# NSE2022_BATTERY_ver0.net
KiCad netlist of a schematic drawn in EAGLE
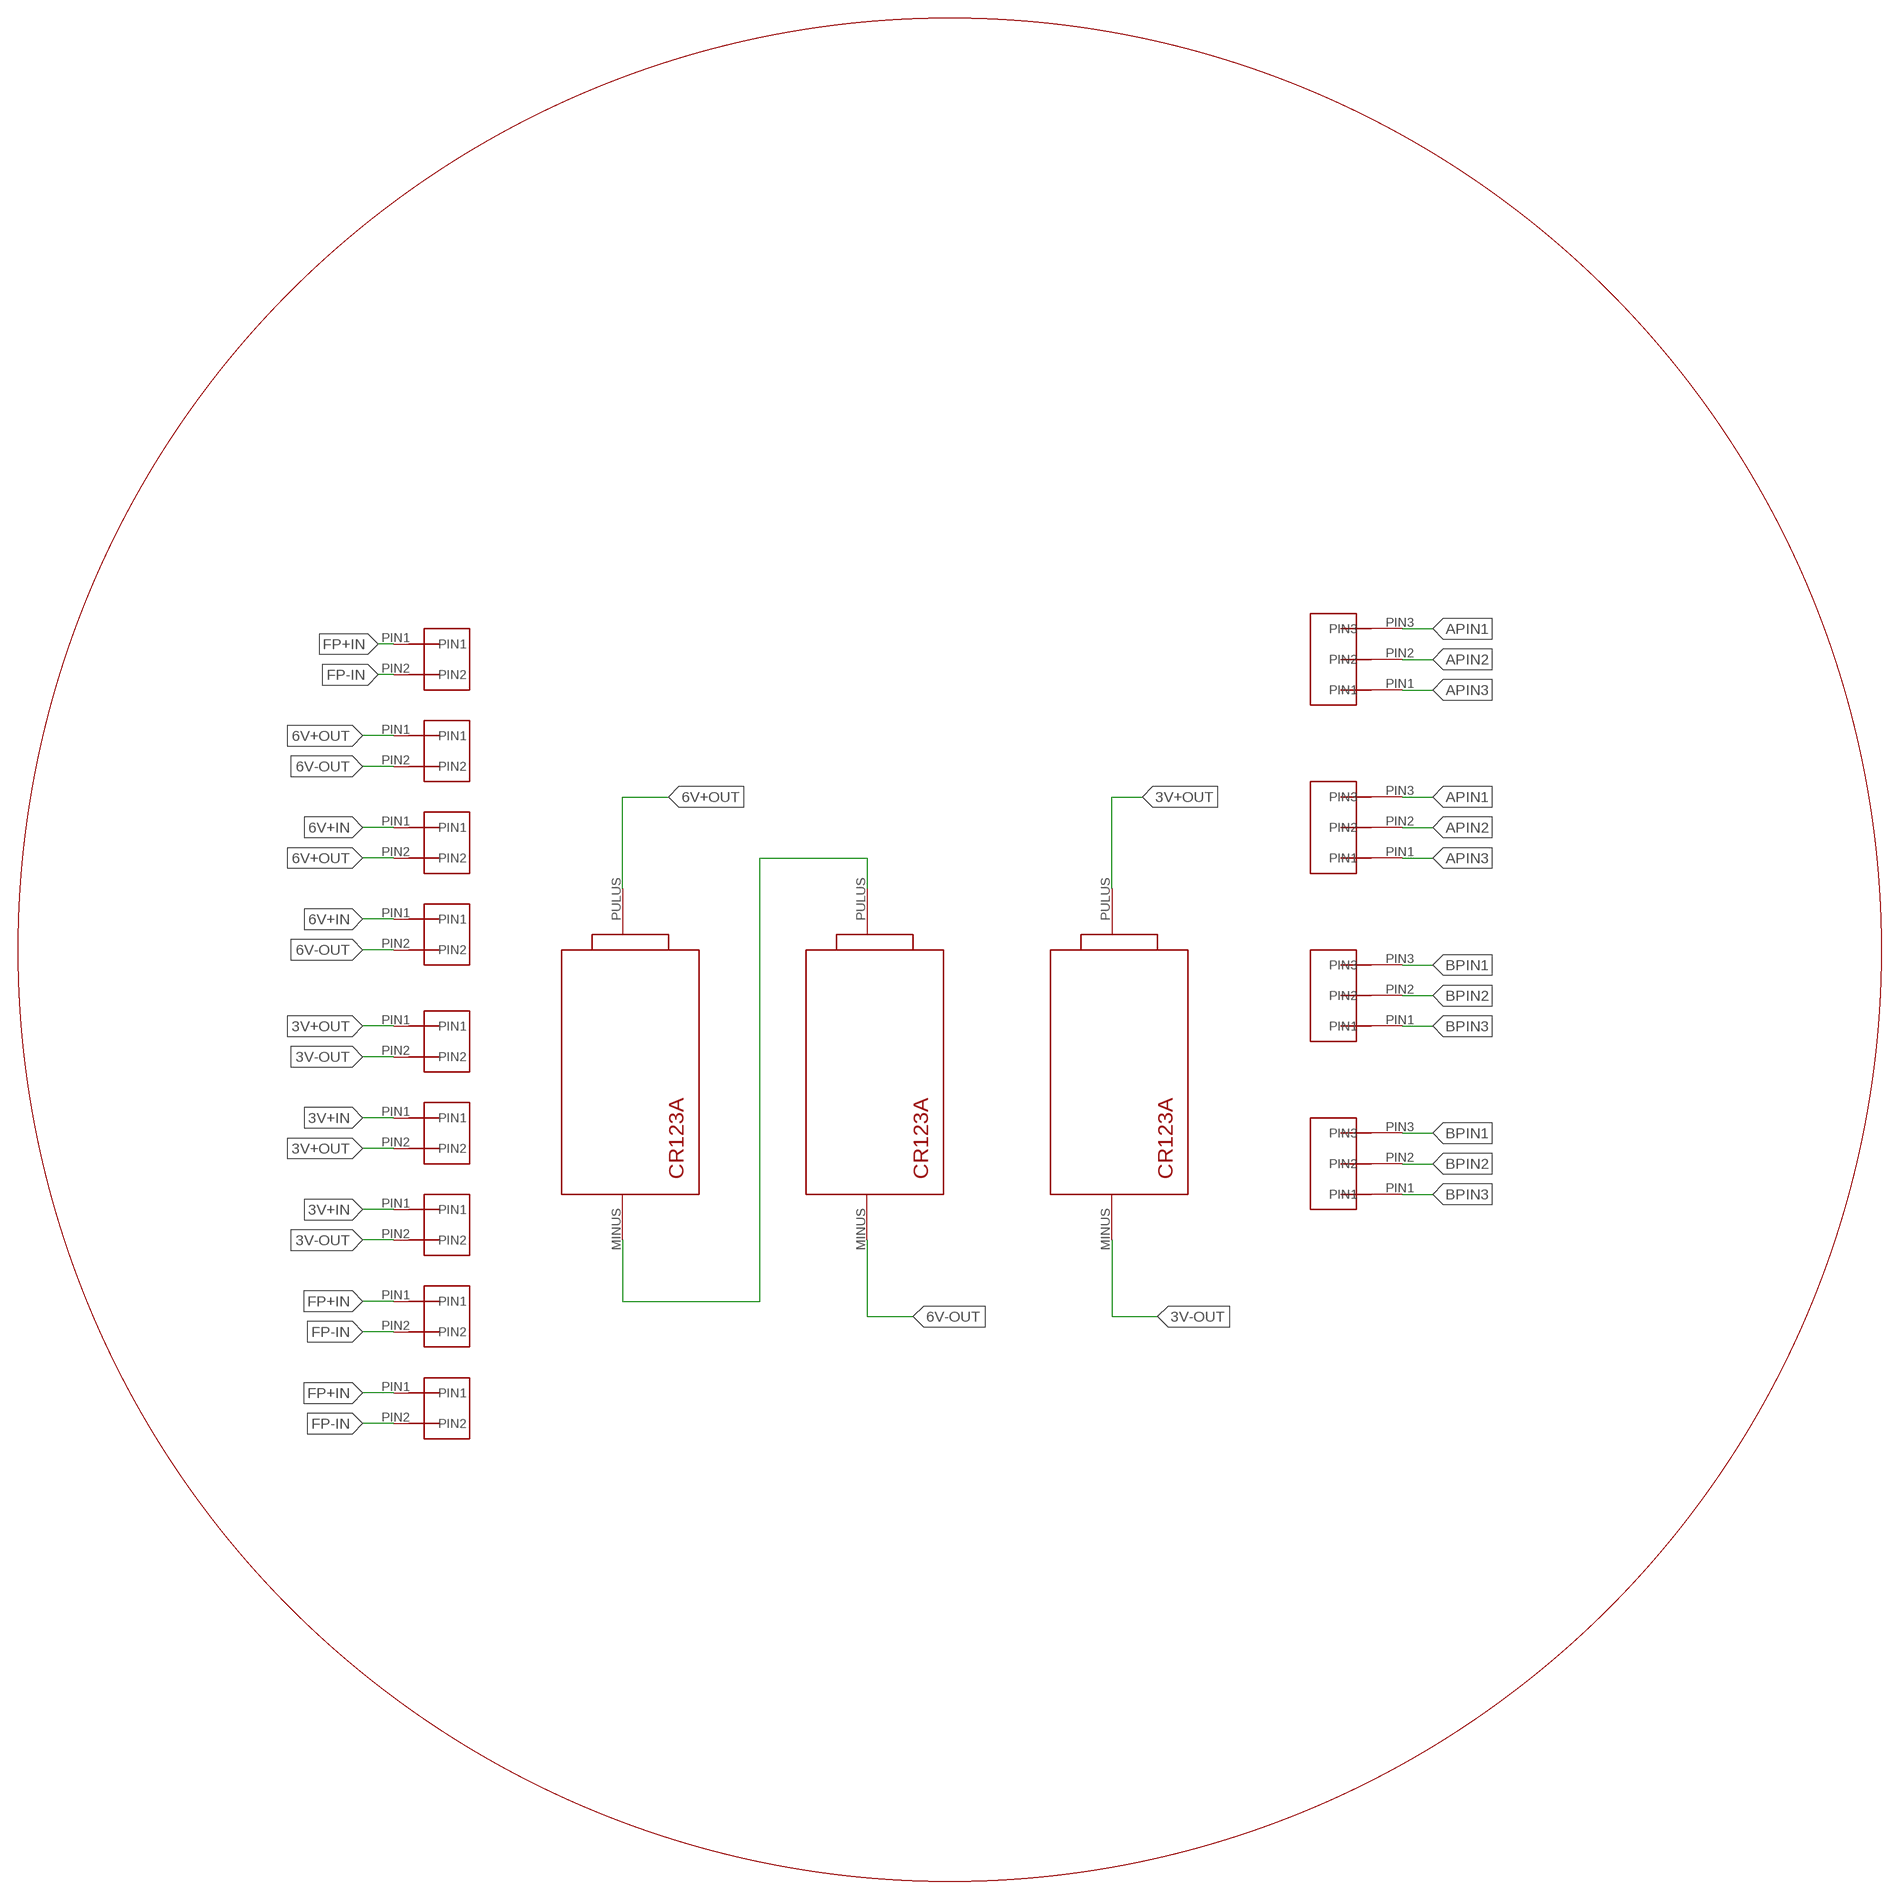
[diagram p0: schematic, sheet 1]

(export (version "E")
  (design (tool "Eeschema 10.0.6"))
  (components
    (comp (ref "U$25")
      (value "CR123A")
      (footprint "eagle-import:CR123A")
      (libsource (lib "eagle-import") (part "CR123A"))
    )
    (comp (ref "U$34")
      (value "CR123A")
      (footprint "eagle-import:CR123A")
      (libsource (lib "eagle-import") (part "CR123A"))
    )
    (comp (ref "U$38")
      (value "CR123A")
      (footprint "eagle-import:CR123A")
      (libsource (lib "eagle-import") (part "CR123A"))
    )
    (comp (ref "U$41")
      (value "2PIN")
      (footprint "eagle-import:2PIN")
      (libsource (lib "eagle-import") (part "2PIN"))
    )
    (comp (ref "U$45")
      (value "2PIN")
      (footprint "eagle-import:2PIN")
      (libsource (lib "eagle-import") (part "2PIN"))
    )
    (comp (ref "U$56")
      (value "2PIN")
      (footprint "eagle-import:2PIN")
      (libsource (lib "eagle-import") (part "2PIN"))
    )
    (comp (ref "U$57")
      (value "2PIN")
      (footprint "eagle-import:2PIN")
      (libsource (lib "eagle-import") (part "2PIN"))
    )
    (comp (ref "U$58")
      (value "2PIN")
      (footprint "eagle-import:2PIN")
      (libsource (lib "eagle-import") (part "2PIN"))
    )
    (comp (ref "U$59")
      (value "3PIN")
      (footprint "eagle-import:3PIN")
      (libsource (lib "eagle-import") (part "3PIN"))
    )
    (comp (ref "U$60")
      (value "3PIN")
      (footprint "eagle-import:3PIN")
      (libsource (lib "eagle-import") (part "3PIN"))
    )
    (comp (ref "U$61")
      (value "3PIN")
      (footprint "eagle-import:3PIN")
      (libsource (lib "eagle-import") (part "3PIN"))
    )
    (comp (ref "U$62")
      (value "3PIN")
      (footprint "eagle-import:3PIN")
      (libsource (lib "eagle-import") (part "3PIN"))
    )
    (comp (ref "U$65")
      (value "2PIN")
      (footprint "eagle-import:2PIN")
      (libsource (lib "eagle-import") (part "2PIN"))
    )
    (comp (ref "U$66")
      (value "2PIN")
      (footprint "eagle-import:2PIN")
      (libsource (lib "eagle-import") (part "2PIN"))
    )
    (comp (ref "U$67")
      (value "2PIN")
      (footprint "eagle-import:2PIN")
      (libsource (lib "eagle-import") (part "2PIN"))
    )
    (comp (ref "U$68")
      (value "2PIN")
      (footprint "eagle-import:2PIN")
      (libsource (lib "eagle-import") (part "2PIN"))
    )
  )
  (nets
    (net (code "1") (name "3V+IN") (class "Default")
      (node (ref "U$56") (pin "PIN1") (pinfunction "PIN1_PIN1") (pintype "bidirectional"))
      (node (ref "U$65") (pin "PIN1") (pinfunction "PIN1_PIN1") (pintype "bidirectional"))
    )
    (net (code "2") (name "3V+OUT") (class "Default")
      (node (ref "U$38") (pin "PULUS") (pinfunction "PULAS_PULUS") (pintype "bidirectional"))
      (node (ref "U$45") (pin "PIN1") (pinfunction "PIN1_PIN1") (pintype "bidirectional"))
      (node (ref "U$56") (pin "PIN2") (pinfunction "PIN2_PIN2") (pintype "bidirectional"))
    )
    (net (code "3") (name "3V-OUT") (class "Default")
      (node (ref "U$38") (pin "MINUS") (pinfunction "MINUS_MINUS") (pintype "bidirectional"))
      (node (ref "U$45") (pin "PIN2") (pinfunction "PIN2_PIN2") (pintype "bidirectional"))
      (node (ref "U$65") (pin "PIN2") (pinfunction "PIN2_PIN2") (pintype "bidirectional"))
    )
    (net (code "4") (name "6V+IN") (class "Default")
      (node (ref "U$67") (pin "PIN1") (pinfunction "PIN1_PIN1") (pintype "bidirectional"))
      (node (ref "U$68") (pin "PIN1") (pinfunction "PIN1_PIN1") (pintype "bidirectional"))
    )
    (net (code "5") (name "6V+OUT") (class "Default")
      (node (ref "U$25") (pin "PULUS") (pinfunction "PULAS_PULUS") (pintype "bidirectional"))
      (node (ref "U$41") (pin "PIN1") (pinfunction "PIN1_PIN1") (pintype "bidirectional"))
      (node (ref "U$67") (pin "PIN2") (pinfunction "PIN2_PIN2") (pintype "bidirectional"))
    )
    (net (code "6") (name "6V-OUT") (class "Default")
      (node (ref "U$34") (pin "MINUS") (pinfunction "MINUS_MINUS") (pintype "bidirectional"))
      (node (ref "U$41") (pin "PIN2") (pinfunction "PIN2_PIN2") (pintype "bidirectional"))
      (node (ref "U$68") (pin "PIN2") (pinfunction "PIN2_PIN2") (pintype "bidirectional"))
    )
    (net (code "7") (name "APIN1") (class "Default")
      (node (ref "U$59") (pin "PIN3") (pinfunction "PIN3_PIN3") (pintype "bidirectional"))
      (node (ref "U$60") (pin "PIN3") (pinfunction "PIN3_PIN3") (pintype "bidirectional"))
    )
    (net (code "8") (name "APIN2") (class "Default")
      (node (ref "U$59") (pin "PIN2") (pinfunction "PIN2_PIN2") (pintype "bidirectional"))
      (node (ref "U$60") (pin "PIN2") (pinfunction "PIN2_PIN2") (pintype "bidirectional"))
    )
    (net (code "9") (name "APIN3") (class "Default")
      (node (ref "U$59") (pin "PIN1") (pinfunction "PIN1_PIN1") (pintype "bidirectional"))
      (node (ref "U$60") (pin "PIN1") (pinfunction "PIN1_PIN1") (pintype "bidirectional"))
    )
    (net (code "10") (name "BPIN1") (class "Default")
      (node (ref "U$61") (pin "PIN3") (pinfunction "PIN3_PIN3") (pintype "bidirectional"))
      (node (ref "U$62") (pin "PIN3") (pinfunction "PIN3_PIN3") (pintype "bidirectional"))
    )
    (net (code "11") (name "BPIN2") (class "Default")
      (node (ref "U$61") (pin "PIN2") (pinfunction "PIN2_PIN2") (pintype "bidirectional"))
      (node (ref "U$62") (pin "PIN2") (pinfunction "PIN2_PIN2") (pintype "bidirectional"))
    )
    (net (code "12") (name "BPIN3") (class "Default")
      (node (ref "U$61") (pin "PIN1") (pinfunction "PIN1_PIN1") (pintype "bidirectional"))
      (node (ref "U$62") (pin "PIN1") (pinfunction "PIN1_PIN1") (pintype "bidirectional"))
    )
    (net (code "13") (name "FP+IN") (class "Default")
      (node (ref "U$57") (pin "PIN1") (pinfunction "PIN1_PIN1") (pintype "bidirectional"))
      (node (ref "U$58") (pin "PIN1") (pinfunction "PIN1_PIN1") (pintype "bidirectional"))
      (node (ref "U$66") (pin "PIN1") (pinfunction "PIN1_PIN1") (pintype "bidirectional"))
    )
    (net (code "14") (name "FP-IN") (class "Default")
      (node (ref "U$57") (pin "PIN2") (pinfunction "PIN2_PIN2") (pintype "bidirectional"))
      (node (ref "U$58") (pin "PIN2") (pinfunction "PIN2_PIN2") (pintype "bidirectional"))
      (node (ref "U$66") (pin "PIN2") (pinfunction "PIN2_PIN2") (pintype "bidirectional"))
    )
    (net (code "15") (name "Net-(U$34-PULAS)") (class "Default")
      (node (ref "U$25") (pin "MINUS") (pinfunction "MINUS_MINUS") (pintype "bidirectional"))
      (node (ref "U$34") (pin "PULUS") (pinfunction "PULAS_PULUS") (pintype "bidirectional"))
    )
  )
)
